# Encoder.net
KiCad netlist of a schematic drawn in EAGLE
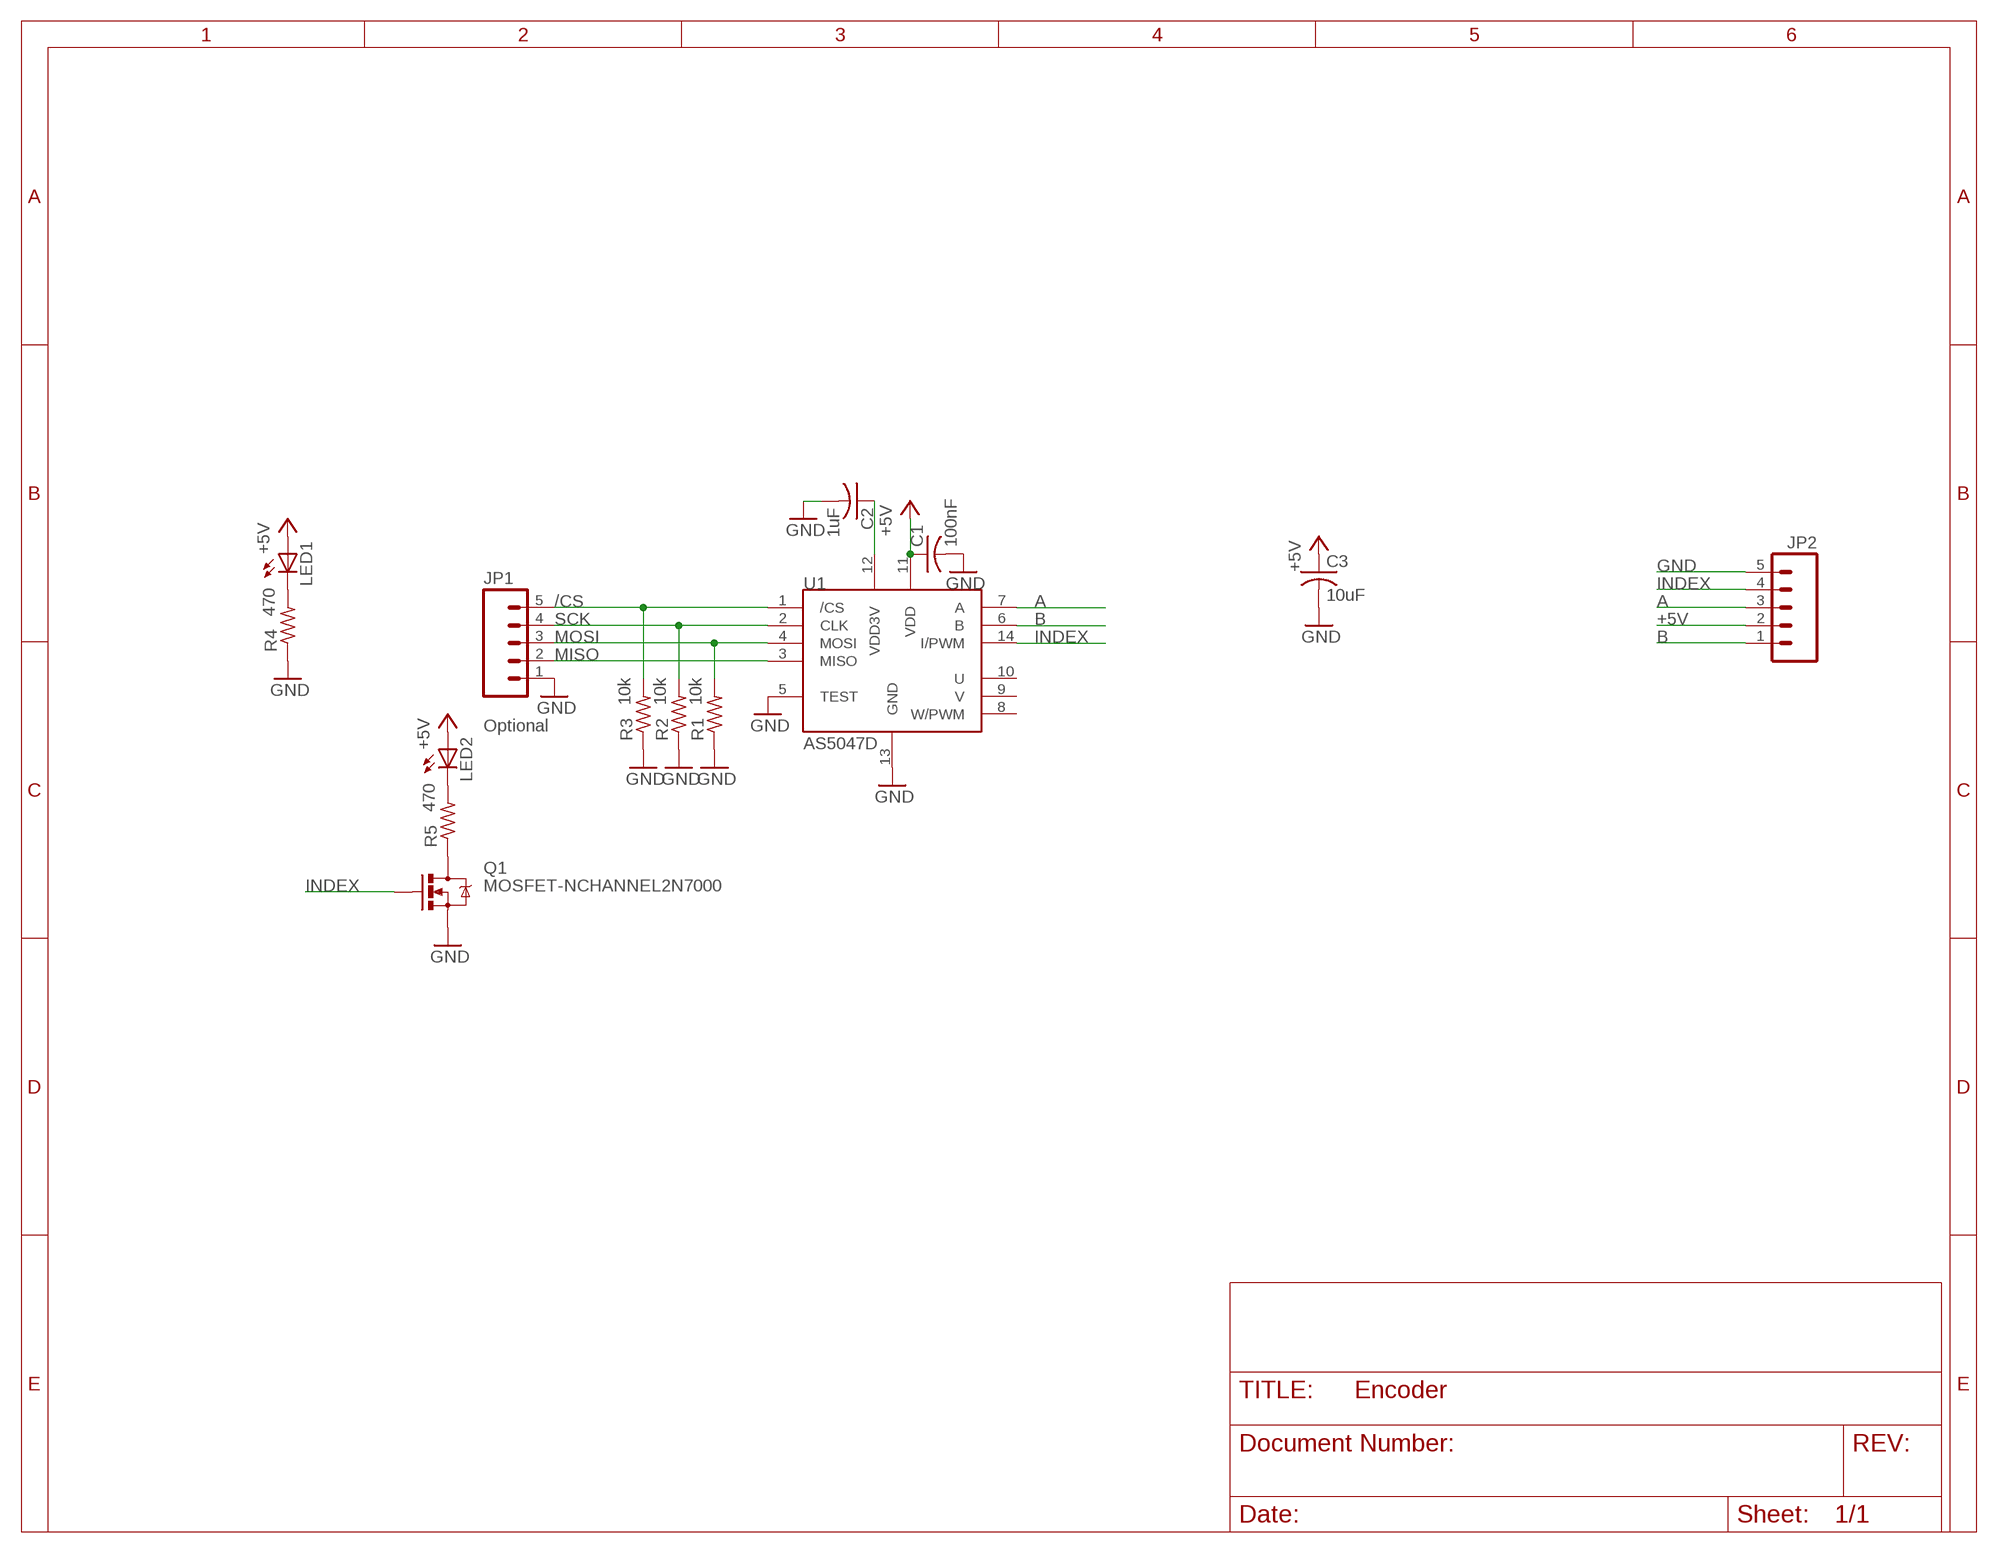
[diagram p0: schematic, sheet 1]

(export (version "E")
  (design (tool "Eeschema 10.0.6"))
  (components
    (comp (ref "C1")
      (value "100nF")
      (footprint "eagle-import:C0603")
      (libsource (lib "eagle-import") (part "C-USC0603"))
    )
    (comp (ref "C2")
      (value "1uF")
      (footprint "eagle-import:C0603")
      (libsource (lib "eagle-import") (part "C-USC0603"))
    )
    (comp (ref "C3")
      (value "10uF")
      (footprint "eagle-import:C0603")
      (libsource (lib "eagle-import") (part "C-USC0603"))
    )
    (comp (ref "JP1")
      (value "M05PTH")
      (footprint "eagle-import:1X05")
      (libsource (lib "eagle-import") (part "M05PTH"))
    )
    (comp (ref "JP2")
      (value "M05PTH")
      (footprint "eagle-import:1X05")
      (libsource (lib "eagle-import") (part "M05PTH"))
    )
    (comp (ref "LED1")
      (value "LED-3MM-NO_SILK")
      (footprint "eagle-import:LED3MM-NS")
      (libsource (lib "eagle-import") (part "LED-3MM-NO_SILK"))
    )
    (comp (ref "LED2")
      (value "LED-3MM-NO_SILK")
      (footprint "eagle-import:LED3MM-NS")
      (libsource (lib "eagle-import") (part "LED-3MM-NO_SILK"))
    )
    (comp (ref "Q1")
      (value "MOSFET-NCHANNEL2N7000")
      (footprint "eagle-import:TO-92")
      (libsource (lib "eagle-import") (part "MOSFET-NCHANNEL2N7000"))
    )
    (comp (ref "R1")
      (value "10k")
      (footprint "eagle-import:R0603")
      (libsource (lib "eagle-import") (part "R-US_R0603"))
    )
    (comp (ref "R2")
      (value "10k")
      (footprint "eagle-import:R0603")
      (libsource (lib "eagle-import") (part "R-US_R0603"))
    )
    (comp (ref "R3")
      (value "10k")
      (footprint "eagle-import:R0603")
      (libsource (lib "eagle-import") (part "R-US_R0603"))
    )
    (comp (ref "R4")
      (value "470")
      (footprint "eagle-import:R0603")
      (libsource (lib "eagle-import") (part "R-US_R0603"))
    )
    (comp (ref "R5")
      (value "470")
      (footprint "eagle-import:R0603")
      (libsource (lib "eagle-import") (part "R-US_R0603"))
    )
    (comp (ref "U1")
      (value "AS5047D")
      (footprint "eagle-import:TSSOP14")
      (libsource (lib "eagle-import") (part "AS5047D"))
    )
  )
  (nets
    (net (code "1") (name "+5V") (class "Default")
      (node (ref "C1") (pin "1") (pinfunction "1_1") (pintype "passive"))
      (node (ref "C3") (pin "1") (pinfunction "1_1") (pintype "passive"))
      (node (ref "JP2") (pin "2") (pinfunction "2_2") (pintype "passive"))
      (node (ref "LED1") (pin "A") (pinfunction "A_A") (pintype "passive"))
      (node (ref "LED2") (pin "A") (pinfunction "A_A") (pintype "passive"))
      (node (ref "U1") (pin "11") (pinfunction "VDD_11") (pintype "bidirectional"))
    )
    (net (code "2") (name "/A") (class "Default")
      (node (ref "JP2") (pin "3") (pinfunction "3_3") (pintype "passive"))
      (node (ref "U1") (pin "7") (pinfunction "A_7") (pintype "bidirectional"))
    )
    (net (code "3") (name "/B") (class "Default")
      (node (ref "JP2") (pin "1") (pinfunction "1_1") (pintype "passive"))
      (node (ref "U1") (pin "6") (pinfunction "B_6") (pintype "bidirectional"))
    )
    (net (code "4") (name "/INDEX") (class "Default")
      (node (ref "JP2") (pin "4") (pinfunction "4_4") (pintype "passive"))
      (node (ref "Q1") (pin "2") (pinfunction "G_2") (pintype "passive"))
      (node (ref "U1") (pin "14") (pinfunction "I/PWM_14") (pintype "bidirectional"))
    )
    (net (code "5") (name "/MISO") (class "Default")
      (node (ref "JP1") (pin "2") (pinfunction "2_2") (pintype "passive"))
      (node (ref "U1") (pin "3") (pinfunction "MISO_3") (pintype "bidirectional"))
    )
    (net (code "6") (name "/MOSI") (class "Default")
      (node (ref "JP1") (pin "3") (pinfunction "3_3") (pintype "passive"))
      (node (ref "R1") (pin "2") (pinfunction "2_2") (pintype "passive"))
      (node (ref "U1") (pin "4") (pinfunction "MOSI_4") (pintype "bidirectional"))
    )
    (net (code "7") (name "/SCK") (class "Default")
      (node (ref "JP1") (pin "4") (pinfunction "4_4") (pintype "passive"))
      (node (ref "R2") (pin "2") (pinfunction "2_2") (pintype "passive"))
      (node (ref "U1") (pin "2") (pinfunction "CLK_2") (pintype "bidirectional"))
    )
    (net (code "8") (name "/{slash}CS") (class "Default")
      (node (ref "JP1") (pin "5") (pinfunction "5_5") (pintype "passive"))
      (node (ref "R3") (pin "2") (pinfunction "2_2") (pintype "passive"))
      (node (ref "U1") (pin "1") (pinfunction "/CS_1") (pintype "bidirectional"))
    )
    (net (code "9") (name "GND") (class "Default")
      (node (ref "C1") (pin "2") (pinfunction "2_2") (pintype "passive"))
      (node (ref "C2") (pin "2") (pinfunction "2_2") (pintype "passive"))
      (node (ref "C3") (pin "2") (pinfunction "2_2") (pintype "passive"))
      (node (ref "JP1") (pin "1") (pinfunction "1_1") (pintype "passive"))
      (node (ref "JP2") (pin "5") (pinfunction "5_5") (pintype "passive"))
      (node (ref "Q1") (pin "1") (pinfunction "S_1") (pintype "passive"))
      (node (ref "R1") (pin "1") (pinfunction "1_1") (pintype "passive"))
      (node (ref "R2") (pin "1") (pinfunction "1_1") (pintype "passive"))
      (node (ref "R3") (pin "1") (pinfunction "1_1") (pintype "passive"))
      (node (ref "R4") (pin "1") (pinfunction "1_1") (pintype "passive"))
      (node (ref "U1") (pin "13") (pinfunction "GND_13") (pintype "bidirectional"))
      (node (ref "U1") (pin "5") (pinfunction "TEST_5") (pintype "bidirectional"))
    )
    (net (code "10") (name "Net-(LED1-C)") (class "Default")
      (node (ref "LED1") (pin "K") (pinfunction "C_K") (pintype "passive"))
      (node (ref "R4") (pin "2") (pinfunction "2_2") (pintype "passive"))
    )
    (net (code "11") (name "Net-(LED2-C)") (class "Default")
      (node (ref "LED2") (pin "K") (pinfunction "C_K") (pintype "passive"))
      (node (ref "R5") (pin "2") (pinfunction "2_2") (pintype "passive"))
    )
    (net (code "12") (name "Net-(Q1-D)") (class "Default")
      (node (ref "Q1") (pin "3") (pinfunction "D_3") (pintype "passive"))
      (node (ref "R5") (pin "1") (pinfunction "1_1") (pintype "passive"))
    )
    (net (code "13") (name "Net-(U1-VDD3V)") (class "Default")
      (node (ref "C2") (pin "1") (pinfunction "1_1") (pintype "passive"))
      (node (ref "U1") (pin "12") (pinfunction "VDD3V_12") (pintype "bidirectional"))
    )
    (net (code "14") (name "unconnected-(U1-U-Pad10)") (class "Default")
      (node (ref "U1") (pin "10") (pinfunction "U_10") (pintype "bidirectional"))
    )
    (net (code "15") (name "unconnected-(U1-V-Pad9)") (class "Default")
      (node (ref "U1") (pin "9") (pinfunction "V_9") (pintype "bidirectional"))
    )
    (net (code "16") (name "unconnected-(U1-W{slash}PWM-Pad8)") (class "Default")
      (node (ref "U1") (pin "8") (pinfunction "W/PWM_8") (pintype "bidirectional"))
    )
  )
)
